# flashlight-boost.net
KiCad netlist of a schematic drawn in EAGLE
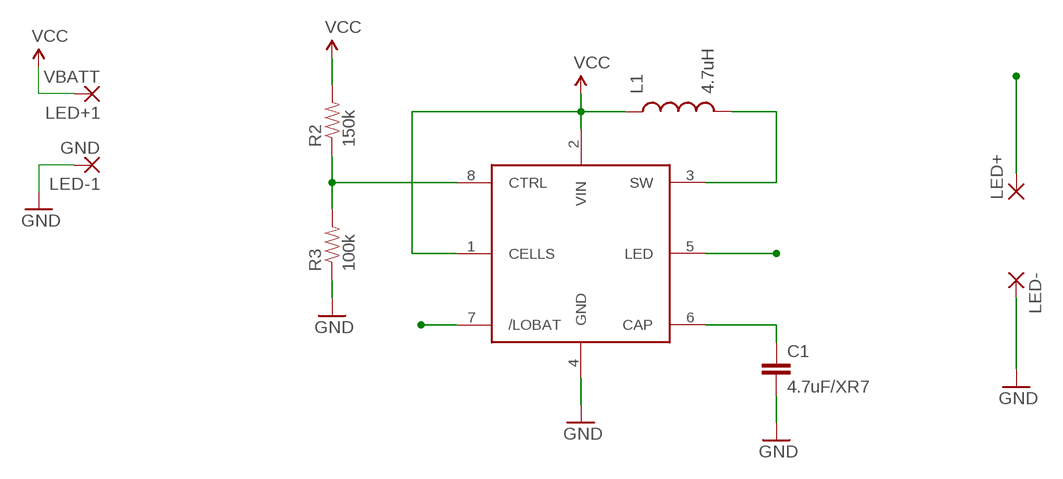
[diagram p0: schematic, sheet 1]

(export (version "E")
  (design (tool "Eeschema 10.0.6"))
  (components
    (comp (ref "C1")
      (value "4.7uF/XR7")
      (footprint "eagle-import:1206")
      (libsource (lib "eagle-import") (part "CAP1206"))
    )
    (comp (ref "L1")
      (value "4.7uH")
      (footprint "eagle-import:1210")
      (libsource (lib "eagle-import") (part "INDUCTOR1210"))
    )
    (comp (ref "LED+")
      (value "2,54/1,0")
      (footprint "eagle-import:2,54_1,0")
      (libsource (lib "eagle-import") (part "2,54/1,0"))
    )
    (comp (ref "LED+1")
      (value "VBATT")
      (footprint "eagle-import:2,54_1,0")
      (libsource (lib "eagle-import") (part "2,54/1,0"))
    )
    (comp (ref "LED-")
      (value "2,54/1,0")
      (footprint "eagle-import:2,54_1,0")
      (libsource (lib "eagle-import") (part "2,54/1,0"))
    )
    (comp (ref "LED-1")
      (value "GND")
      (footprint "eagle-import:2,54_1,0")
      (libsource (lib "eagle-import") (part "2,54/1,0"))
    )
    (comp (ref "R2")
      (value "150k")
      (footprint "eagle-import:0603-RES")
      (libsource (lib "eagle-import") (part "RESISTOR0603-RES"))
    )
    (comp (ref "R3")
      (value "100k")
      (footprint "eagle-import:0603-RES")
      (libsource (lib "eagle-import") (part "RESISTOR0603-RES"))
    )
    (comp (ref "U$1")
      (value "LTC3490NSOIC-8")
      (footprint "eagle-import:NSOIC-8")
      (libsource (lib "eagle-import") (part "LTC3490NSOIC-8"))
    )
  )
  (nets
    (net (code "1") (name "/LED") (class "Default")
      (node (ref "LED+") (pin "1") (pinfunction "P_1") (pintype "passive"))
      (node (ref "U$1") (pin "5") (pinfunction "LED_5") (pintype "bidirectional"))
    )
    (net (code "2") (name "GND") (class "Default")
      (node (ref "C1") (pin "2") (pinfunction "2_2") (pintype "passive"))
      (node (ref "LED-") (pin "1") (pinfunction "P_1") (pintype "passive"))
      (node (ref "LED-1") (pin "1") (pinfunction "P_1") (pintype "passive"))
      (node (ref "R3") (pin "1") (pinfunction "1_1") (pintype "passive"))
      (node (ref "U$1") (pin "4") (pinfunction "GND_4") (pintype "bidirectional"))
    )
    (net (code "3") (name "Net-(U$1-CAP)") (class "Default")
      (node (ref "C1") (pin "1") (pinfunction "1_1") (pintype "passive"))
      (node (ref "U$1") (pin "6") (pinfunction "CAP_6") (pintype "bidirectional"))
    )
    (net (code "4") (name "Net-(U$1-CTRL)") (class "Default")
      (node (ref "R2") (pin "1") (pinfunction "1_1") (pintype "passive"))
      (node (ref "R3") (pin "2") (pinfunction "2_2") (pintype "passive"))
      (node (ref "U$1") (pin "8") (pinfunction "CTRL_8") (pintype "bidirectional"))
    )
    (net (code "5") (name "Net-(U$1-SW)") (class "Default")
      (node (ref "L1") (pin "2") (pinfunction "2_2") (pintype "passive"))
      (node (ref "U$1") (pin "3") (pinfunction "SW_3") (pintype "bidirectional"))
    )
    (net (code "6") (name "VCC") (class "Default")
      (node (ref "L1") (pin "1") (pinfunction "1_1") (pintype "passive"))
      (node (ref "LED+1") (pin "1") (pinfunction "P_1") (pintype "passive"))
      (node (ref "R2") (pin "2") (pinfunction "2_2") (pintype "passive"))
      (node (ref "U$1") (pin "1") (pinfunction "CELLS_1") (pintype "bidirectional"))
      (node (ref "U$1") (pin "2") (pinfunction "VIN_2") (pintype "bidirectional"))
    )
    (net (code "7") (name "unconnected-(U$1-{slash}LOBAT-Pad7)") (class "Default")
      (node (ref "U$1") (pin "7") (pinfunction "/LOBAT_7") (pintype "bidirectional"))
    )
  )
)
